# BatteryBalancer_old.net
KiCad netlist of a schematic drawn in EAGLE
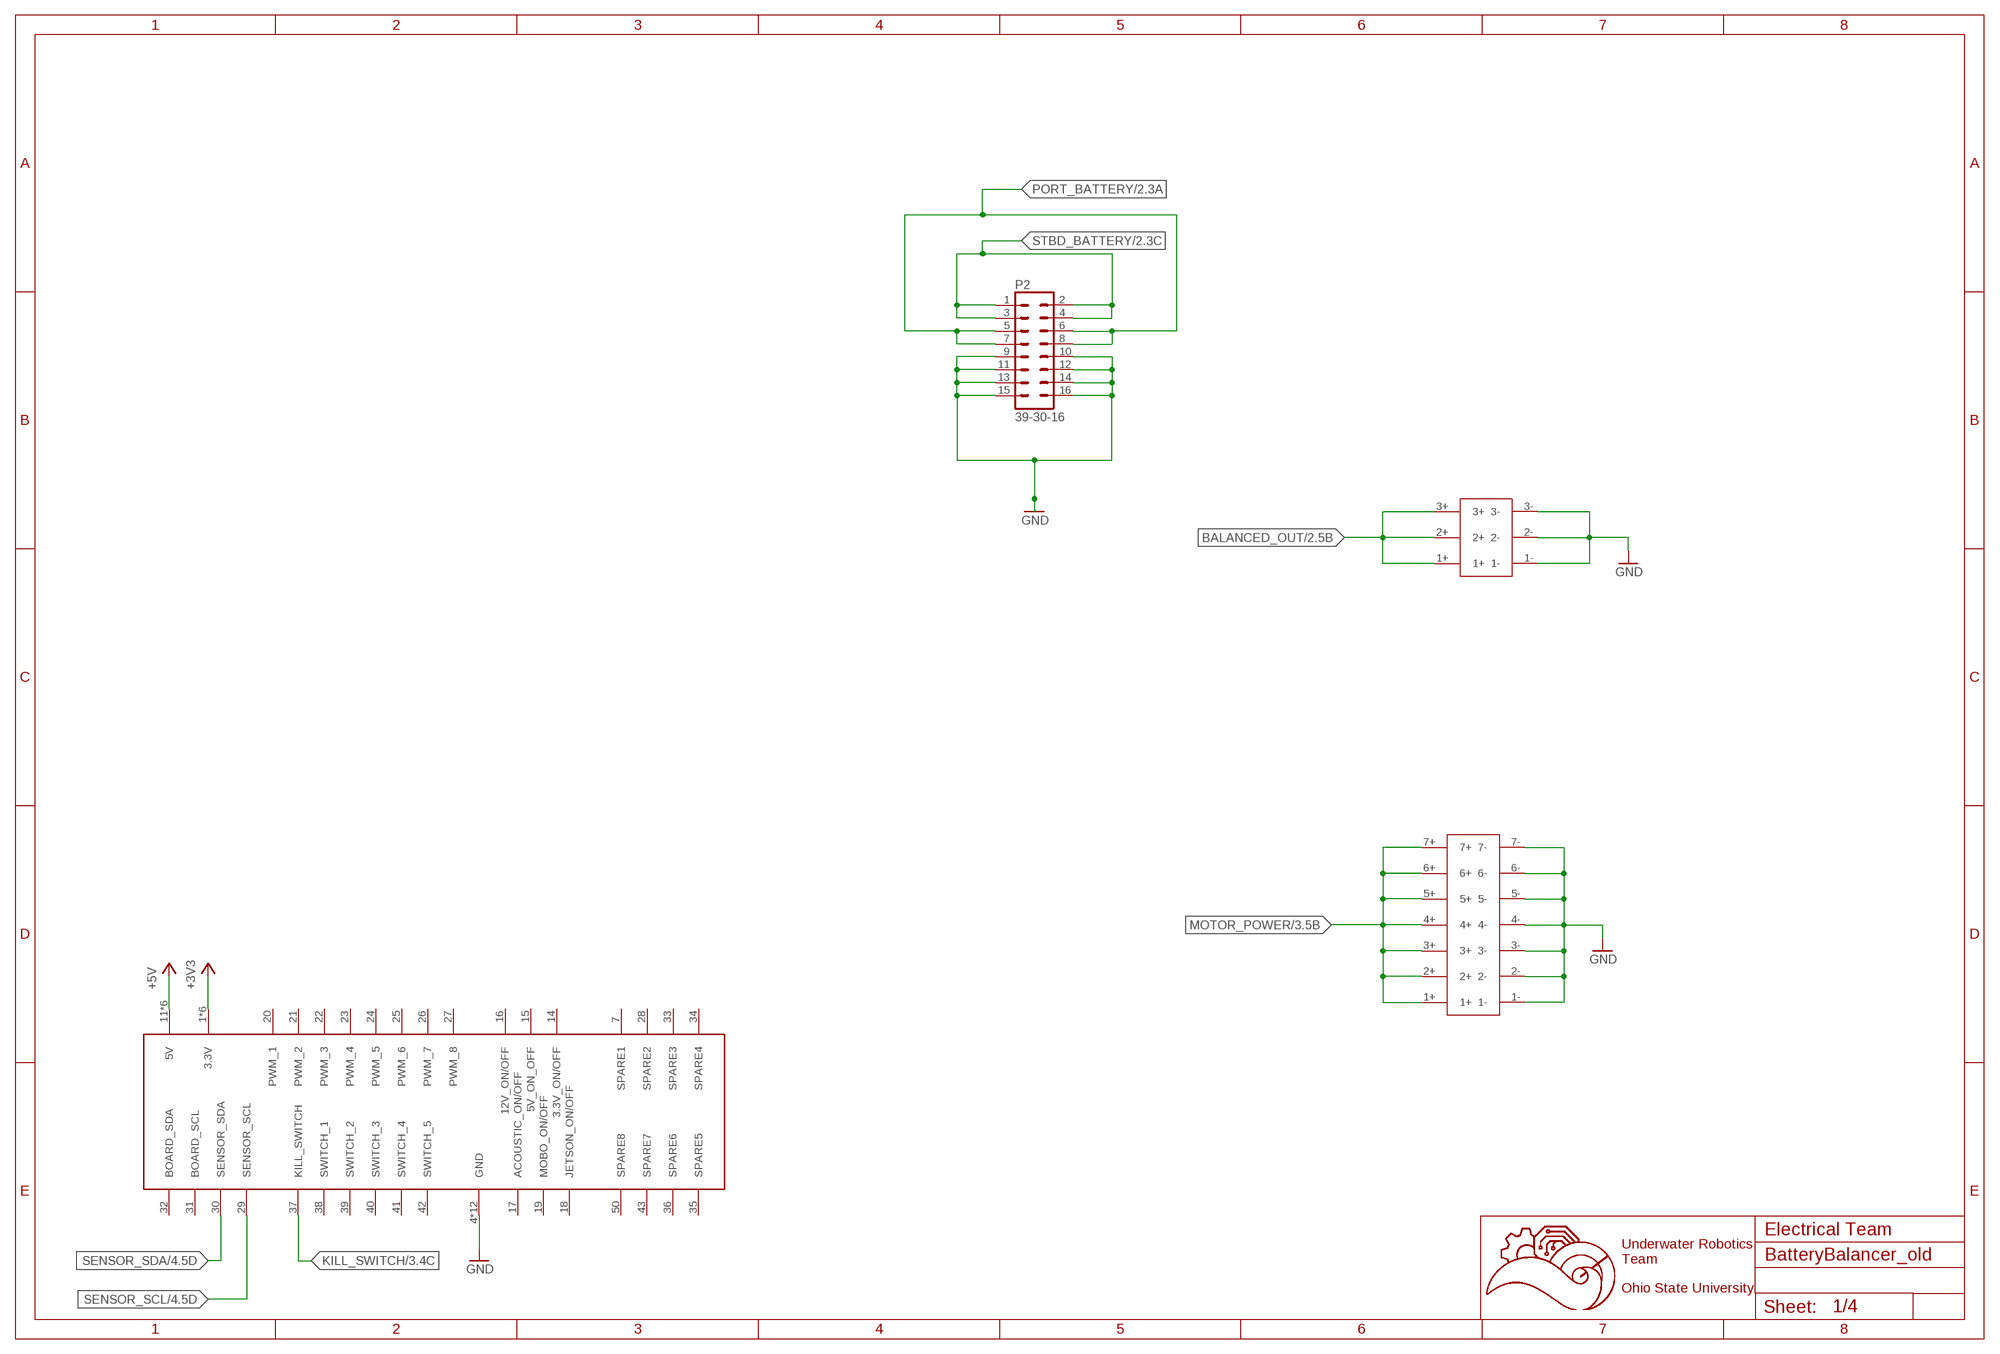
[diagram p0: schematic, sheet 1]
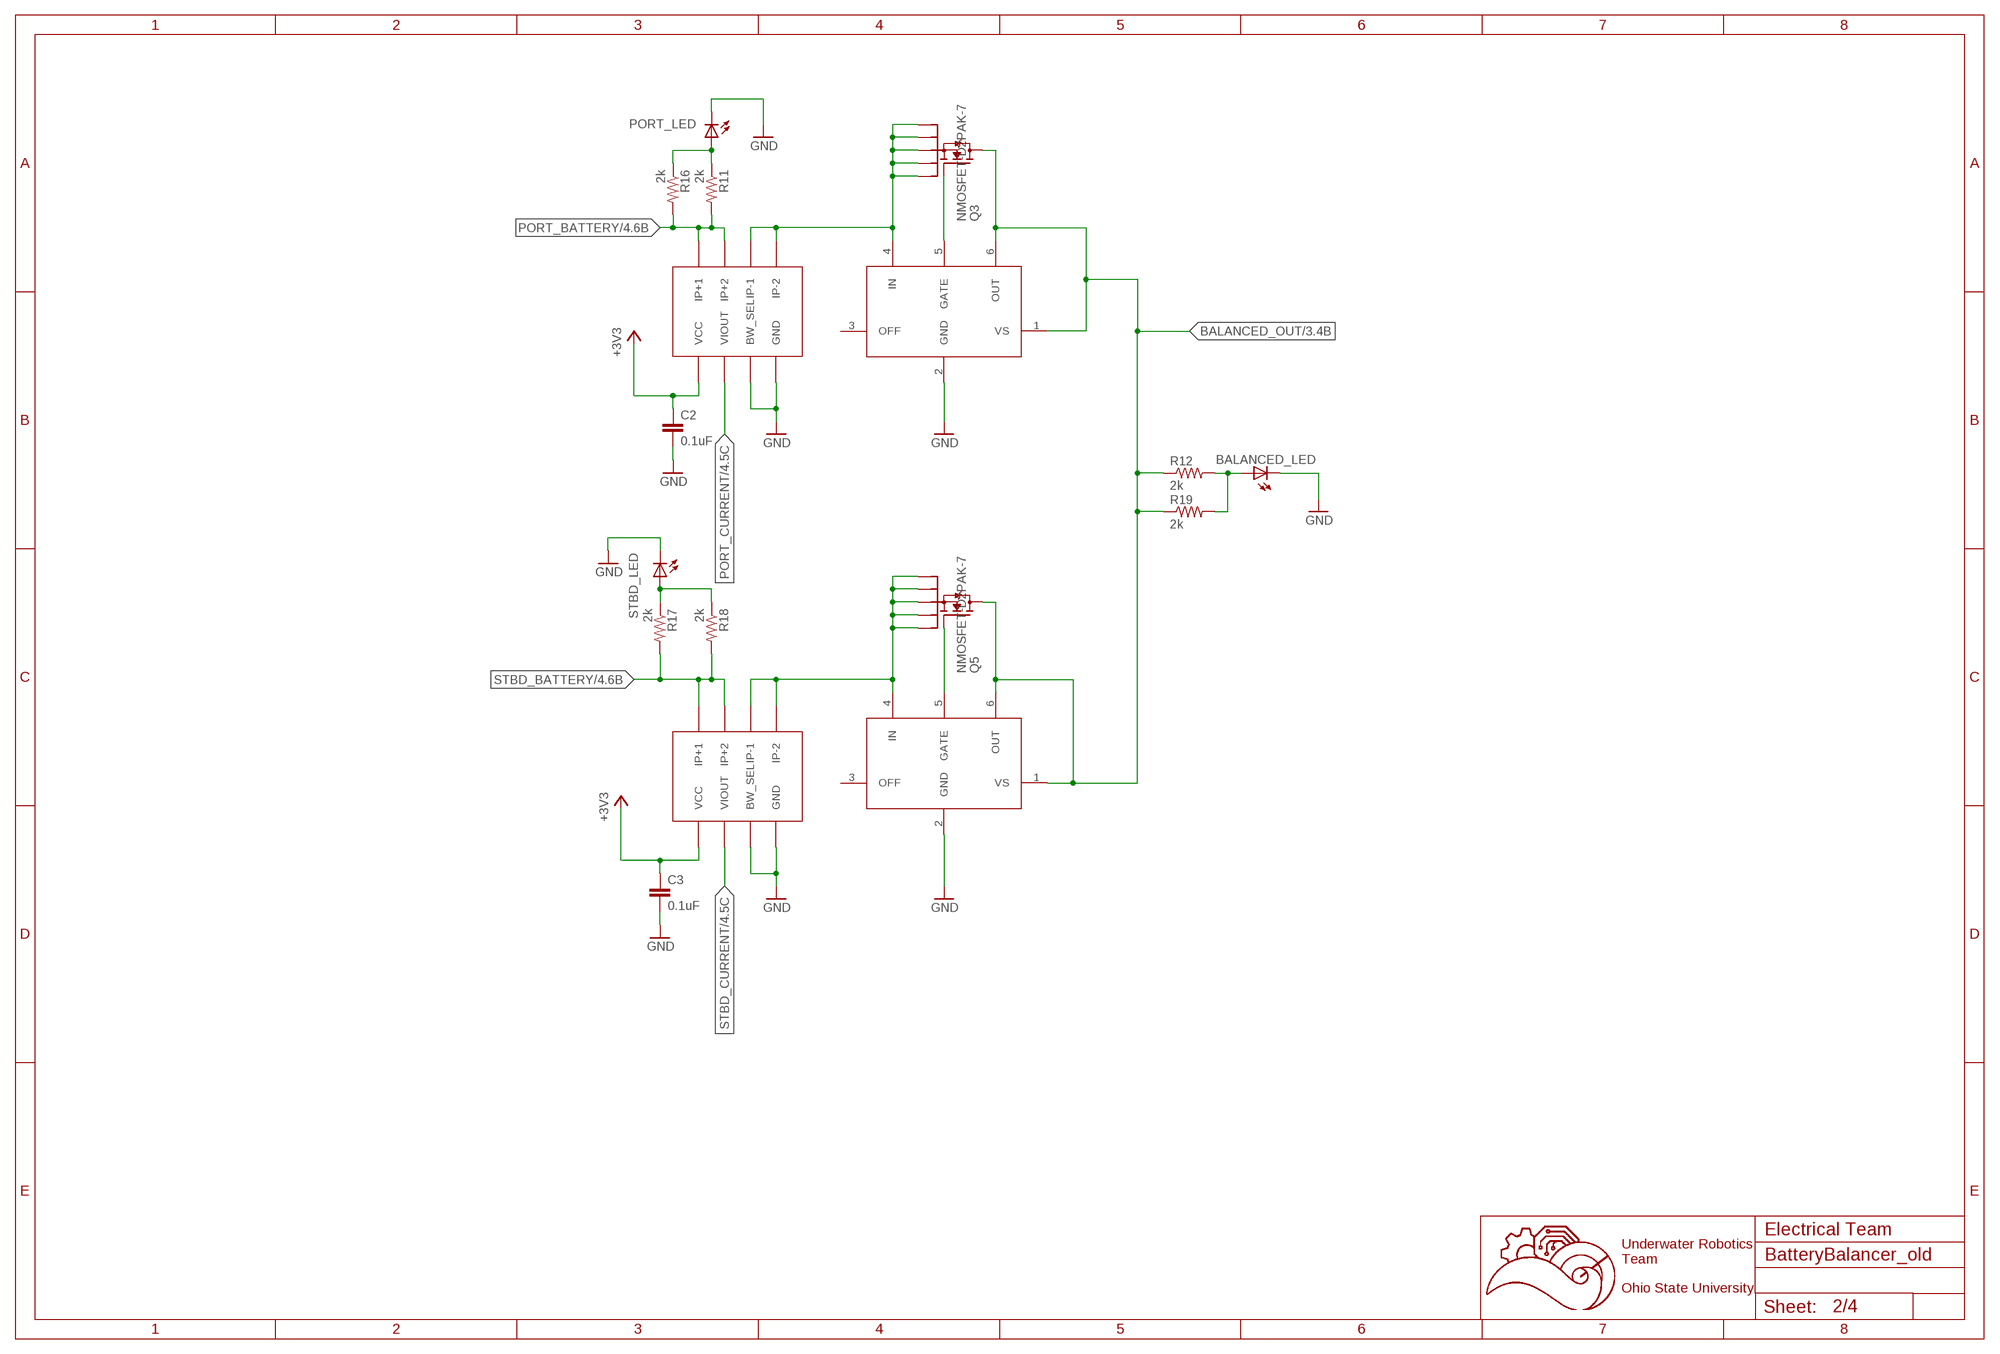
[diagram p1: schematic, sheet 2]
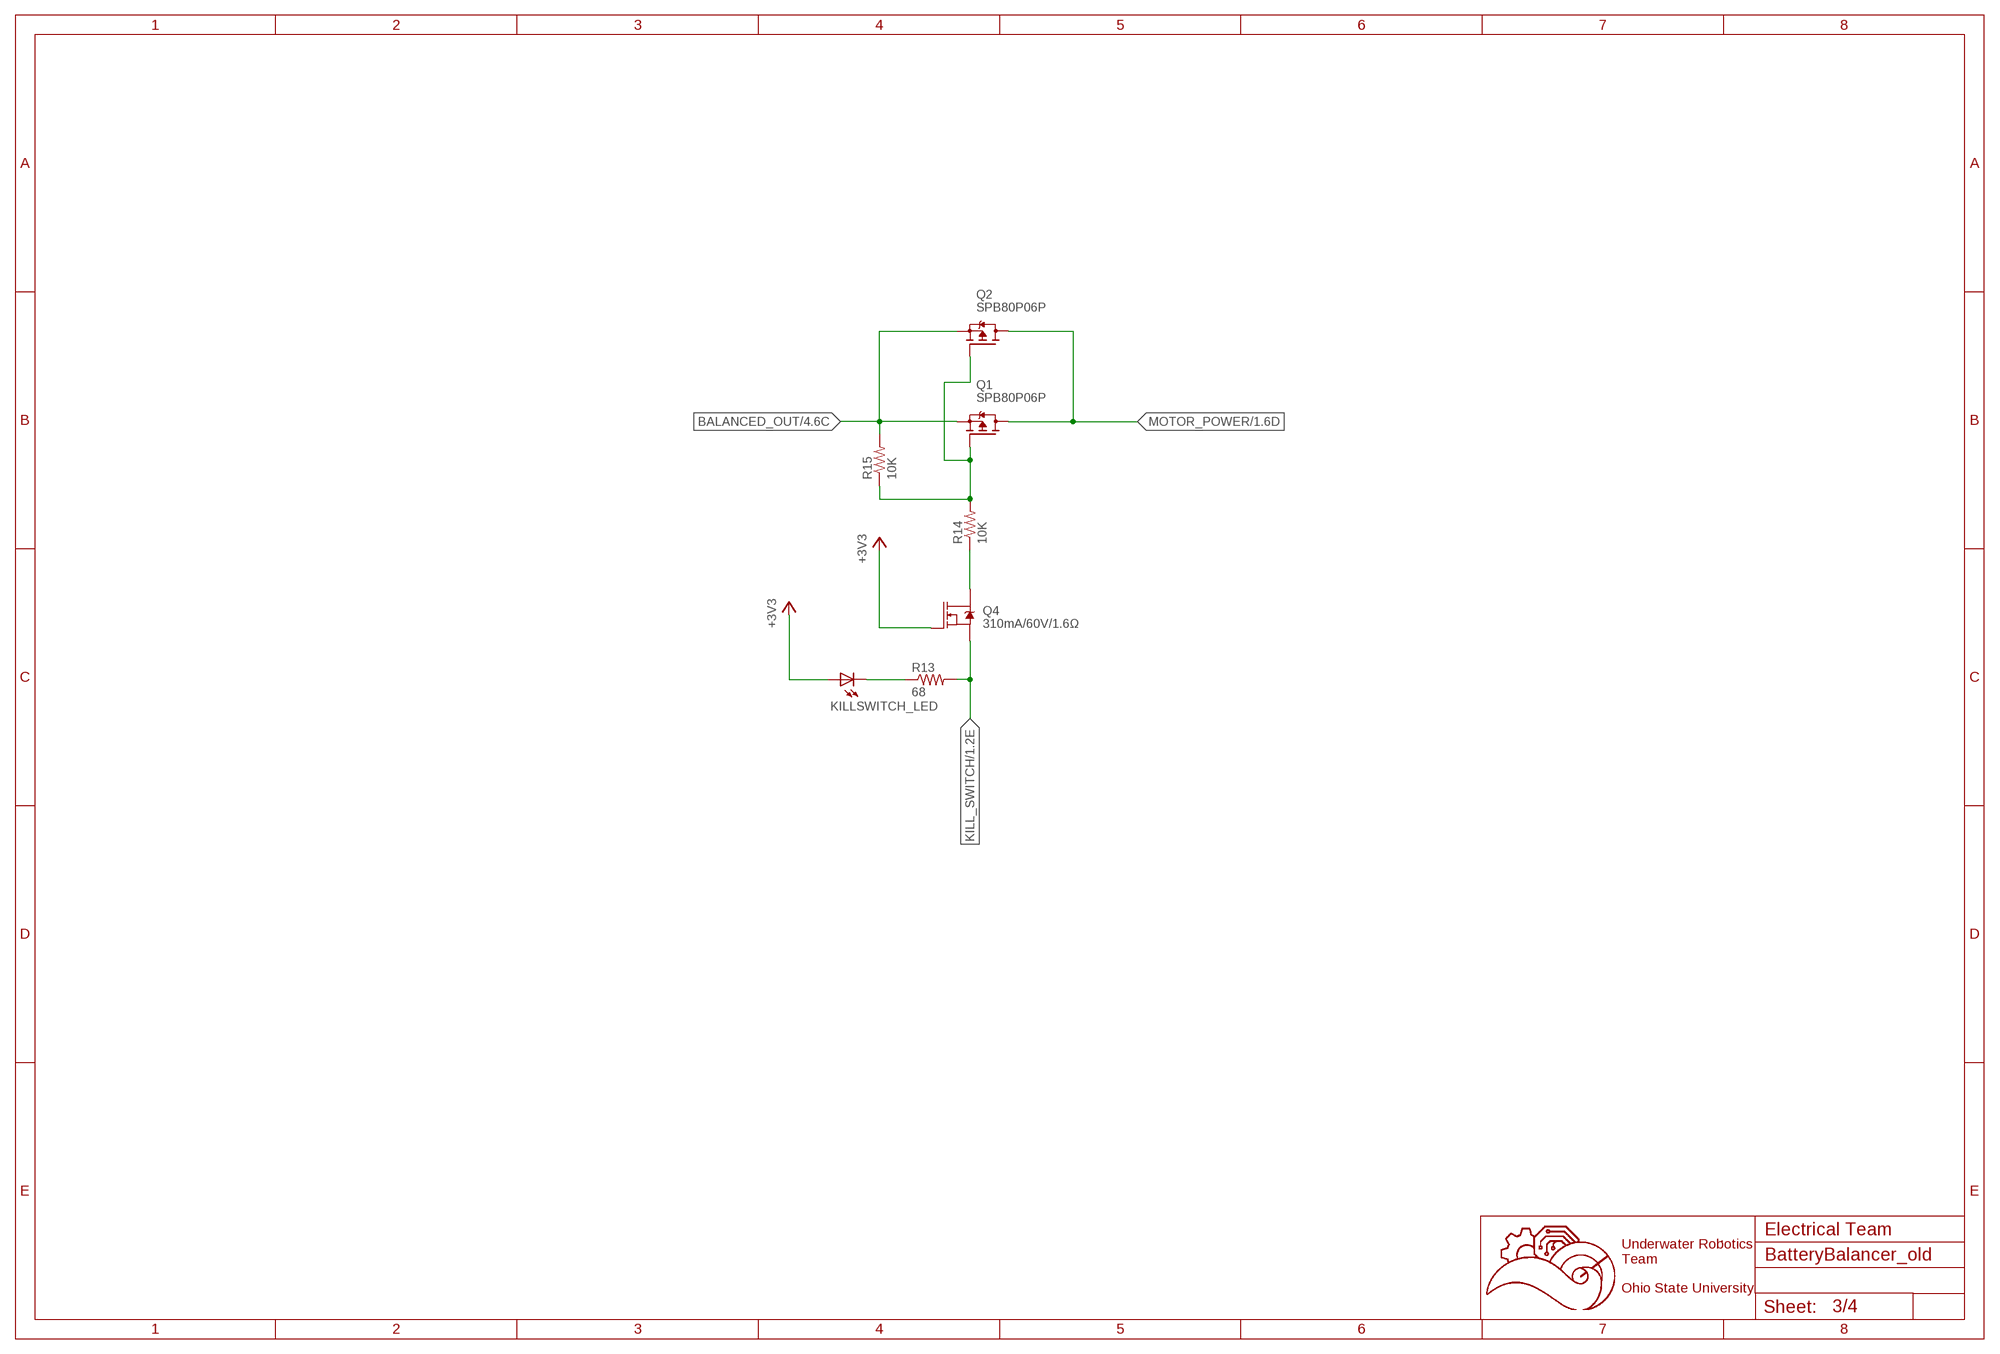
[diagram p2: schematic, sheet 3]
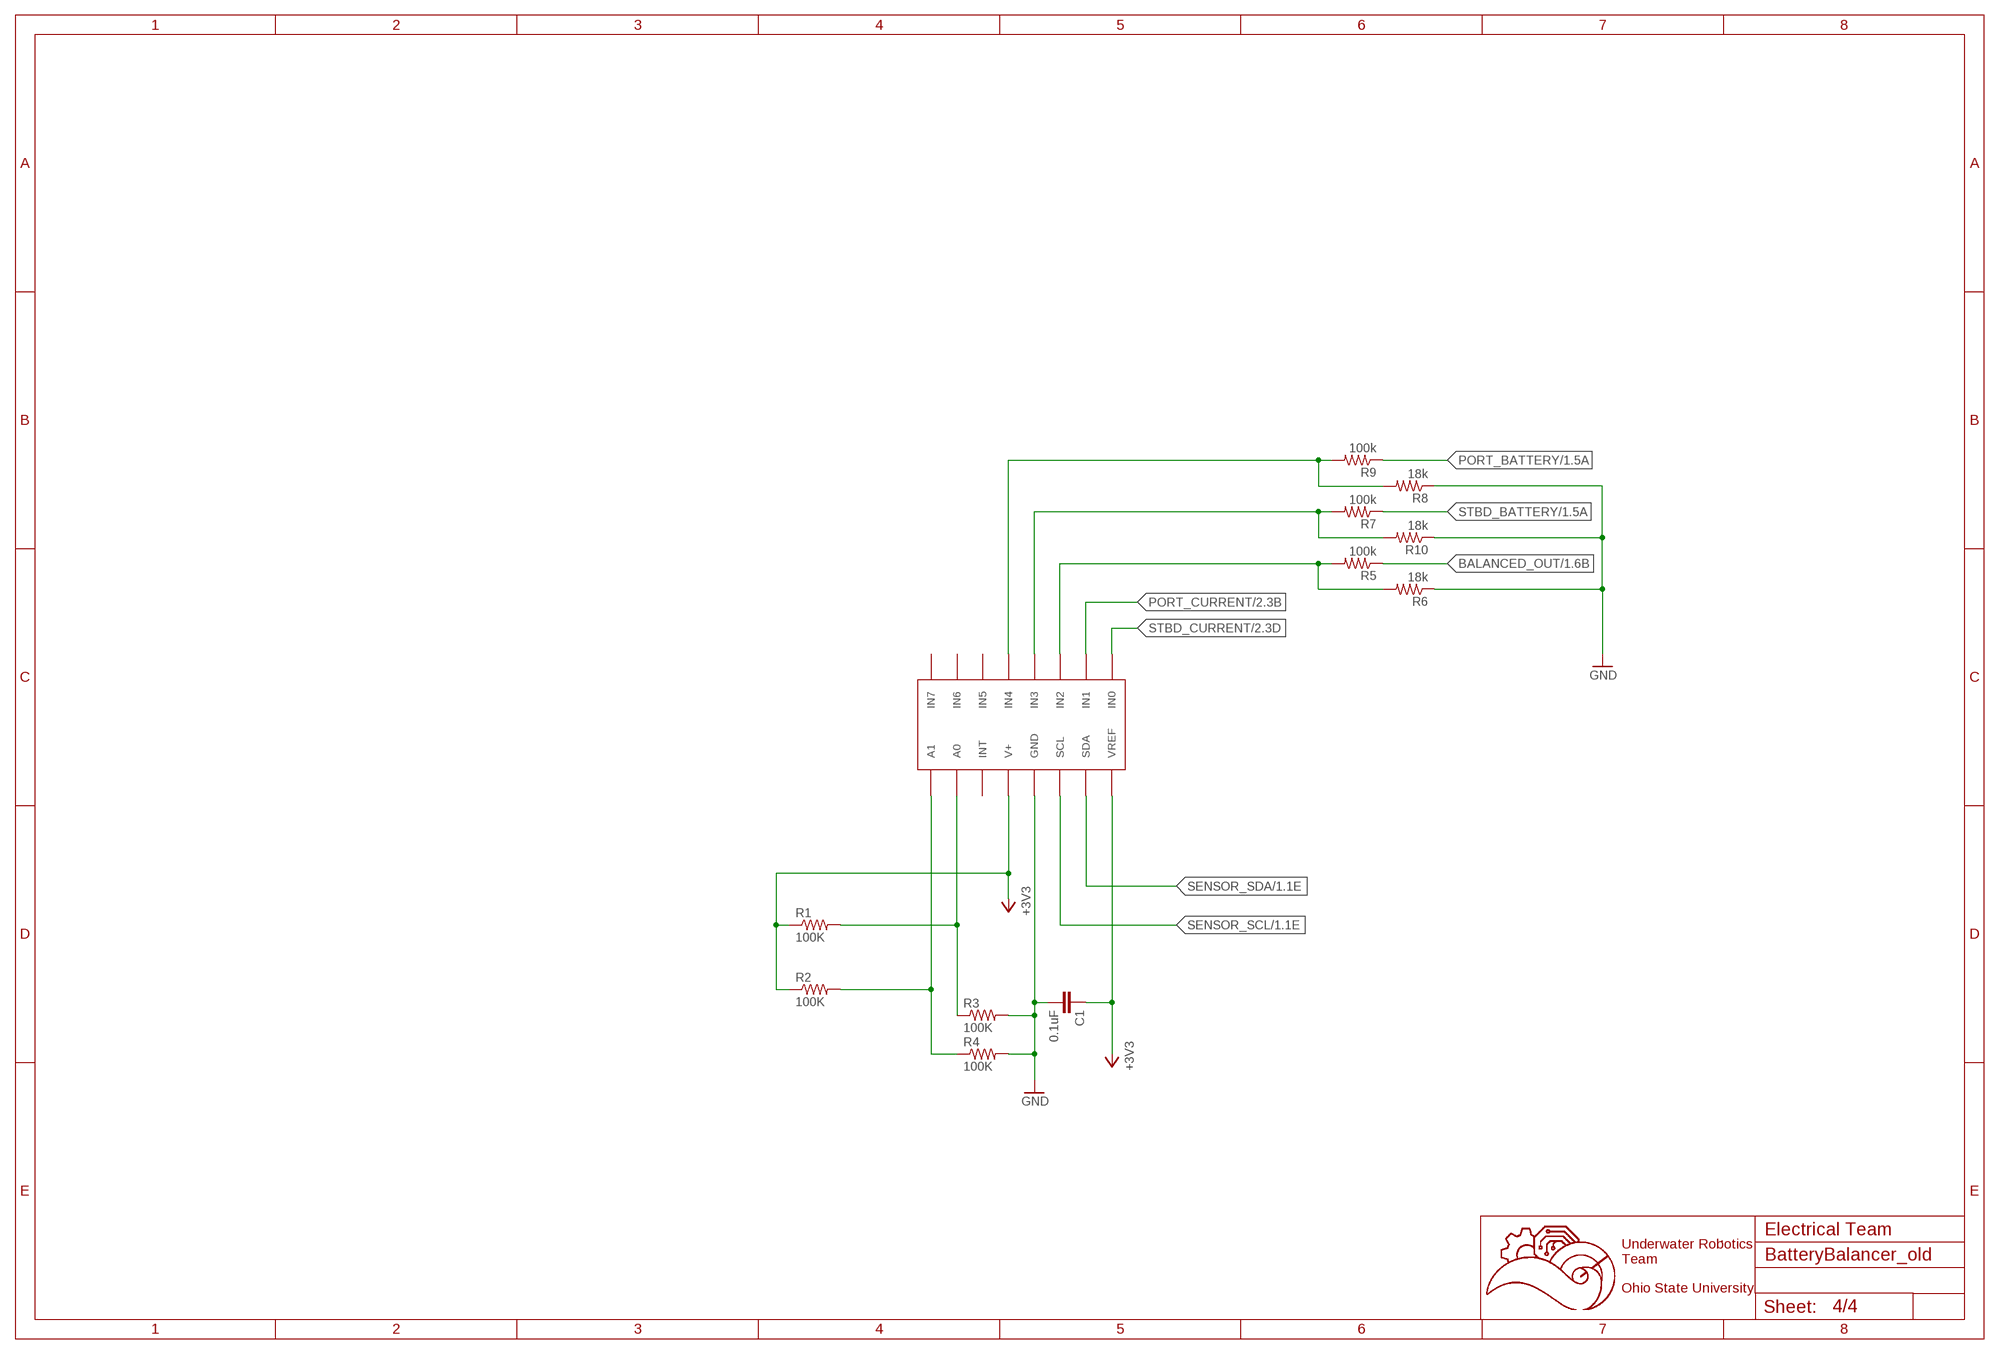
[diagram p3: schematic, sheet 4]

(export (version "E")
  (design (tool "Eeschema 10.0.6"))
  (components
    (comp (ref "C1")
      (value "0.1uF")
      (footprint "eagle-import:C0603")
      (libsource (lib "eagle-import") (part "C-EUC0603"))
    )
    (comp (ref "R1")
      (value "100K")
      (footprint "eagle-import:R0603")
      (libsource (lib "eagle-import") (part "R-US_R0603"))
    )
    (comp (ref "R2")
      (value "100K")
      (footprint "eagle-import:R0603")
      (libsource (lib "eagle-import") (part "R-US_R0603"))
    )
    (comp (ref "R3")
      (value "100K")
      (footprint "eagle-import:R0603")
      (libsource (lib "eagle-import") (part "R-US_R0603"))
    )
    (comp (ref "R4")
      (value "100K")
      (footprint "eagle-import:R0603")
      (libsource (lib "eagle-import") (part "R-US_R0603"))
    )
    (comp (ref "R5")
      (value "100k")
      (footprint "eagle-import:R0603")
      (libsource (lib "eagle-import") (part "R-US_R0603"))
    )
    (comp (ref "R6")
      (value "18k")
      (footprint "eagle-import:R0603")
      (libsource (lib "eagle-import") (part "R-US_R0603"))
    )
    (comp (ref "R7")
      (value "100k")
      (footprint "eagle-import:R0603")
      (libsource (lib "eagle-import") (part "R-US_R0603"))
    )
    (comp (ref "R8")
      (value "18k")
      (footprint "eagle-import:R0603")
      (libsource (lib "eagle-import") (part "R-US_R0603"))
    )
    (comp (ref "R9")
      (value "100k")
      (footprint "eagle-import:R0603")
      (libsource (lib "eagle-import") (part "R-US_R0603"))
    )
    (comp (ref "R10")
      (value "18k")
      (footprint "eagle-import:R0603")
      (libsource (lib "eagle-import") (part "R-US_R0603"))
    )
    (comp (ref "U$12")
      (value "ADC128D818")
      (footprint "eagle-import:TSSOP-16")
      (libsource (lib "eagle-import") (part "ADC128D818"))
    )
    (comp (ref "KILLSWITCH_LED")
      (value "LEDCHIP-LED0603")
      (footprint "eagle-import:CHIP-LED0603")
      (libsource (lib "eagle-import") (part "LEDCHIP-LED0603"))
    )
    (comp (ref "Q1")
      (value "SPB80P06P")
      (footprint "eagle-import:TO263")
      (libsource (lib "eagle-import") (part "SPB80P06P"))
    )
    (comp (ref "Q2")
      (value "SPB80P06P")
      (footprint "eagle-import:TO263")
      (libsource (lib "eagle-import") (part "SPB80P06P"))
    )
    (comp (ref "Q4")
      (value "310mA/60V/1.6Ω")
      (footprint "eagle-import:SOT323")
      (libsource (lib "eagle-import") (part "MOSFET-NCH-2N7002PW"))
    )
    (comp (ref "R13")
      (value "68")
      (footprint "eagle-import:R0603")
      (libsource (lib "eagle-import") (part "R-US_R0603"))
    )
    (comp (ref "R14")
      (value "10K")
      (footprint "eagle-import:R0603")
      (libsource (lib "eagle-import") (part "R-US_R0603"))
    )
    (comp (ref "R15")
      (value "10K")
      (footprint "eagle-import:R0603")
      (libsource (lib "eagle-import") (part "R-US_R0603"))
    )
    (comp (ref "P2")
      (value "39-30-16")
      (footprint "eagle-import:39-30-_16_")
      (libsource (lib "eagle-import") (part "39-30-?16?"))
    )
    (comp (ref "U$1")
      (value "5530843-EDGE")
      (footprint "eagle-import:5530843-6-BOARDFINGERS")
      (libsource (lib "eagle-import") (part "5530843-EDGE"))
    )
    (comp (ref "U$4")
      (value "14PIN-VERT")
      (footprint "eagle-import:14PIN_VERT")
      (libsource (lib "eagle-import") (part "14PIN-VERT"))
    )
    (comp (ref "U$13")
      (value "6PIN-VERT")
      (footprint "eagle-import:6PIN_VERT")
      (libsource (lib "eagle-import") (part "6PIN-VERT"))
    )
    (comp (ref "BALANCED_LED")
      (value "LEDCHIP-LED0603")
      (footprint "eagle-import:CHIP-LED0603")
      (libsource (lib "eagle-import") (part "LEDCHIP-LED0603"))
    )
    (comp (ref "C2")
      (value "0.1uF")
      (footprint "eagle-import:C0603")
      (libsource (lib "eagle-import") (part "C-EUC0603"))
    )
    (comp (ref "C3")
      (value "0.1uF")
      (footprint "eagle-import:C0603")
      (libsource (lib "eagle-import") (part "C-EUC0603"))
    )
    (comp (ref "PORT_LED")
      (value "LEDCHIP-LED0603")
      (footprint "eagle-import:CHIP-LED0603")
      (libsource (lib "eagle-import") (part "LEDCHIP-LED0603"))
    )
    (comp (ref "Q3")
      (value "NMOSFET-D2PAK-7")
      (footprint "eagle-import:D2PAK-7")
      (libsource (lib "eagle-import") (part "NMOSFET-D2PAK-7"))
    )
    (comp (ref "Q5")
      (value "NMOSFET-D2PAK-7")
      (footprint "eagle-import:D2PAK-7")
      (libsource (lib "eagle-import") (part "NMOSFET-D2PAK-7"))
    )
    (comp (ref "R11")
      (value "2k")
      (footprint "eagle-import:R0603")
      (libsource (lib "eagle-import") (part "R-US_R0603"))
    )
    (comp (ref "R12")
      (value "2k")
      (footprint "eagle-import:R0603")
      (libsource (lib "eagle-import") (part "R-US_R0603"))
    )
    (comp (ref "R16")
      (value "2k")
      (footprint "eagle-import:R0603")
      (libsource (lib "eagle-import") (part "R-US_R0603"))
    )
    (comp (ref "R17")
      (value "2k")
      (footprint "eagle-import:R0603")
      (libsource (lib "eagle-import") (part "R-US_R0603"))
    )
    (comp (ref "R18")
      (value "2k")
      (footprint "eagle-import:R0603")
      (libsource (lib "eagle-import") (part "R-US_R0603"))
    )
    (comp (ref "R19")
      (value "2k")
      (footprint "eagle-import:R0603")
      (libsource (lib "eagle-import") (part "R-US_R0603"))
    )
    (comp (ref "STBD_LED")
      (value "LEDCHIP-LED0603")
      (footprint "eagle-import:CHIP-LED0603")
      (libsource (lib "eagle-import") (part "LEDCHIP-LED0603"))
    )
    (comp (ref "U$2")
      (value "LM5050")
      (footprint "eagle-import:LM5050")
      (libsource (lib "eagle-import") (part "LM5050"))
    )
    (comp (ref "U$3")
      (value "LM5050")
      (footprint "eagle-import:LM5050")
      (libsource (lib "eagle-import") (part "LM5050"))
    )
    (comp (ref "U$6")
      (value "ACS722")
      (footprint "eagle-import:SOIC-8")
      (libsource (lib "eagle-import") (part "ACS722"))
    )
    (comp (ref "U$7")
      (value "ACS722")
      (footprint "eagle-import:SOIC-8")
      (libsource (lib "eagle-import") (part "ACS722"))
    )
  )
  (nets
    (net (code "1") (name "+3V3") (class "Default")
      (node (ref "C1") (pin "1") (pinfunction "1_1") (pintype "passive"))
      (node (ref "C2") (pin "1") (pinfunction "1_1") (pintype "passive"))
      (node (ref "C3") (pin "1") (pinfunction "1_1") (pintype "passive"))
      (node (ref "KILLSWITCH_LED") (pin "A") (pinfunction "A_A") (pintype "passive"))
      (node (ref "Q4") (pin "1") (pinfunction "G_1") (pintype "bidirectional"))
      (node (ref "R1") (pin "1") (pinfunction "1_1") (pintype "passive"))
      (node (ref "R2") (pin "1") (pinfunction "1_1") (pintype "passive"))
      (node (ref "U$1") (pin "1") (pinfunction "3.3V_1") (pintype "bidirectional"))
      (node (ref "U$1") (pin "2") (pinfunction "3.3V_2") (pintype "bidirectional"))
      (node (ref "U$1") (pin "3") (pinfunction "3.3V_3") (pintype "bidirectional"))
      (node (ref "U$1") (pin "54") (pinfunction "3.3V_54") (pintype "bidirectional"))
      (node (ref "U$1") (pin "55") (pinfunction "3.3V_55") (pintype "bidirectional"))
      (node (ref "U$1") (pin "56") (pinfunction "3.3V_56") (pintype "bidirectional"))
      (node (ref "U$12") (pin "V+") (pinfunction "V+_V+") (pintype "bidirectional"))
      (node (ref "U$12") (pin "VREF") (pinfunction "VREF_VREF") (pintype "bidirectional"))
      (node (ref "U$6") (pin "VCC") (pinfunction "VCC_VCC") (pintype "bidirectional"))
      (node (ref "U$7") (pin "VCC") (pinfunction "VCC_VCC") (pintype "bidirectional"))
    )
    (net (code "2") (name "+5V") (class "Default")
      (node (ref "U$1") (pin "11") (pinfunction "5V_11") (pintype "bidirectional"))
      (node (ref "U$1") (pin "12") (pinfunction "5V_12") (pintype "bidirectional"))
      (node (ref "U$1") (pin "13") (pinfunction "5V_13") (pintype "bidirectional"))
      (node (ref "U$1") (pin "44") (pinfunction "5V_44") (pintype "bidirectional"))
      (node (ref "U$1") (pin "45") (pinfunction "5V_45") (pintype "bidirectional"))
      (node (ref "U$1") (pin "46") (pinfunction "5V_46") (pintype "bidirectional"))
    )
    (net (code "3") (name "BALANCED_OUT") (class "Default")
      (node (ref "Q1") (pin "2") (pinfunction "S_2") (pintype "passive"))
      (node (ref "Q2") (pin "2") (pinfunction "S_2") (pintype "passive"))
      (node (ref "Q3") (pin "D") (pinfunction "D_D") (pintype "passive"))
      (node (ref "Q5") (pin "D") (pinfunction "D_D") (pintype "passive"))
      (node (ref "R12") (pin "1") (pinfunction "1_1") (pintype "passive"))
      (node (ref "R15") (pin "2") (pinfunction "2_2") (pintype "passive"))
      (node (ref "R19") (pin "1") (pinfunction "1_1") (pintype "passive"))
      (node (ref "R5") (pin "1") (pinfunction "1_1") (pintype "passive"))
      (node (ref "U$13") (pin "1+") (pinfunction "1+_1+") (pintype "bidirectional"))
      (node (ref "U$13") (pin "2+") (pinfunction "2+_2+") (pintype "bidirectional"))
      (node (ref "U$13") (pin "3+") (pinfunction "3+_3+") (pintype "bidirectional"))
      (node (ref "U$2") (pin "1") (pinfunction "VS_1") (pintype "bidirectional"))
      (node (ref "U$2") (pin "6") (pinfunction "OUT_6") (pintype "bidirectional"))
      (node (ref "U$3") (pin "1") (pinfunction "VS_1") (pintype "bidirectional"))
      (node (ref "U$3") (pin "6") (pinfunction "OUT_6") (pintype "bidirectional"))
    )
    (net (code "4") (name "GND") (class "Default")
      (node (ref "BALANCED_LED") (pin "C") (pinfunction "C_C") (pintype "passive"))
      (node (ref "C1") (pin "2") (pinfunction "2_2") (pintype "passive"))
      (node (ref "C2") (pin "2") (pinfunction "2_2") (pintype "passive"))
      (node (ref "C3") (pin "2") (pinfunction "2_2") (pintype "passive"))
      (node (ref "P2") (pin "10") (pinfunction "10_10") (pintype "passive"))
      (node (ref "P2") (pin "11") (pinfunction "11_11") (pintype "passive"))
      (node (ref "P2") (pin "12") (pinfunction "12_12") (pintype "passive"))
      (node (ref "P2") (pin "13") (pinfunction "13_13") (pintype "passive"))
      (node (ref "P2") (pin "14") (pinfunction "14_14") (pintype "passive"))
      (node (ref "P2") (pin "15") (pinfunction "15_15") (pintype "passive"))
      (node (ref "P2") (pin "16") (pinfunction "16_16") (pintype "passive"))
      (node (ref "P2") (pin "9") (pinfunction "9_9") (pintype "passive"))
      (node (ref "PORT_LED") (pin "C") (pinfunction "C_C") (pintype "passive"))
      (node (ref "R10") (pin "1") (pinfunction "1_1") (pintype "passive"))
      (node (ref "R3") (pin "2") (pinfunction "2_2") (pintype "passive"))
      (node (ref "R4") (pin "2") (pinfunction "2_2") (pintype "passive"))
      (node (ref "R6") (pin "1") (pinfunction "1_1") (pintype "passive"))
      (node (ref "R8") (pin "1") (pinfunction "1_1") (pintype "passive"))
      (node (ref "STBD_LED") (pin "C") (pinfunction "C_C") (pintype "passive"))
      (node (ref "U$1") (pin "10") (pinfunction "GND_10") (pintype "bidirectional"))
      (node (ref "U$1") (pin "4") (pinfunction "GND_4") (pintype "bidirectional"))
      (node (ref "U$1") (pin "47") (pinfunction "GND_47") (pintype "bidirectional"))
      (node (ref "U$1") (pin "48") (pinfunction "GND_48") (pintype "bidirectional"))
      (node (ref "U$1") (pin "49") (pinfunction "GND_49") (pintype "bidirectional"))
      (node (ref "U$1") (pin "5") (pinfunction "GND_5") (pintype "bidirectional"))
      (node (ref "U$1") (pin "51") (pinfunction "GND_51") (pintype "bidirectional"))
      (node (ref "U$1") (pin "52") (pinfunction "GND_52") (pintype "bidirectional"))
      (node (ref "U$1") (pin "53") (pinfunction "GND_53") (pintype "bidirectional"))
      (node (ref "U$1") (pin "6") (pinfunction "GND_6") (pintype "bidirectional"))
      (node (ref "U$1") (pin "8") (pinfunction "GND_8") (pintype "bidirectional"))
      (node (ref "U$1") (pin "9") (pinfunction "GND_9") (pintype "bidirectional"))
      (node (ref "U$12") (pin "GND") (pinfunction "GND_GND") (pintype "bidirectional"))
      (node (ref "U$13") (pin "1-") (pinfunction "1-_1-") (pintype "bidirectional"))
      (node (ref "U$13") (pin "2-") (pinfunction "2-_2-") (pintype "bidirectional"))
      (node (ref "U$13") (pin "3-") (pinfunction "3-_3-") (pintype "bidirectional"))
      (node (ref "U$2") (pin "2") (pinfunction "GND_2") (pintype "bidirectional"))
      (node (ref "U$3") (pin "2") (pinfunction "GND_2") (pintype "bidirectional"))
      (node (ref "U$4") (pin "1-") (pinfunction "1-_1-") (pintype "bidirectional"))
      (node (ref "U$4") (pin "2-") (pinfunction "2-_2-") (pintype "bidirectional"))
      (node (ref "U$4") (pin "3-") (pinfunction "3-_3-") (pintype "bidirectional"))
      (node (ref "U$4") (pin "4-") (pinfunction "4-_4-") (pintype "bidirectional"))
      (node (ref "U$4") (pin "5-") (pinfunction "5-_5-") (pintype "bidirectional"))
      (node (ref "U$4") (pin "6-") (pinfunction "6-_6-") (pintype "bidirectional"))
      (node (ref "U$4") (pin "7-") (pinfunction "7-_7-") (pintype "bidirectional"))
      (node (ref "U$6") (pin "BW_SEL") (pinfunction "BW_SEL_BW_SEL") (pintype "bidirectional"))
      (node (ref "U$6") (pin "GND") (pinfunction "GND_GND") (pintype "bidirectional"))
      (node (ref "U$7") (pin "BW_SEL") (pinfunction "BW_SEL_BW_SEL") (pintype "bidirectional"))
      (node (ref "U$7") (pin "GND") (pinfunction "GND_GND") (pintype "bidirectional"))
    )
    (net (code "5") (name "KILL_SWITCH") (class "Default")
      (node (ref "Q4") (pin "2") (pinfunction "S_2") (pintype "bidirectional"))
      (node (ref "R13") (pin "2") (pinfunction "2_2") (pintype "passive"))
      (node (ref "U$1") (pin "37") (pinfunction "KILL_SWITCH_37") (pintype "output"))
    )
    (net (code "6") (name "MOTOR_POWER") (class "Default")
      (node (ref "Q1") (pin "3") (pinfunction "D_3") (pintype "passive"))
      (node (ref "Q2") (pin "3") (pinfunction "D_3") (pintype "passive"))
      (node (ref "U$4") (pin "1+") (pinfunction "1+_1+") (pintype "bidirectional"))
      (node (ref "U$4") (pin "2+") (pinfunction "2+_2+") (pintype "bidirectional"))
      (node (ref "U$4") (pin "3+") (pinfunction "3+_3+") (pintype "bidirectional"))
      (node (ref "U$4") (pin "4+") (pinfunction "4+_4+") (pintype "bidirectional"))
      (node (ref "U$4") (pin "5+") (pinfunction "5+_5+") (pintype "bidirectional"))
      (node (ref "U$4") (pin "6+") (pinfunction "6+_6+") (pintype "bidirectional"))
      (node (ref "U$4") (pin "7+") (pinfunction "7+_7+") (pintype "bidirectional"))
    )
    (net (code "7") (name "Net-(BALANCED_LED-PadA)") (class "Default")
      (node (ref "BALANCED_LED") (pin "A") (pinfunction "A_A") (pintype "passive"))
      (node (ref "R12") (pin "2") (pinfunction "2_2") (pintype "passive"))
      (node (ref "R19") (pin "2") (pinfunction "2_2") (pintype "passive"))
    )
    (net (code "8") (name "Net-(KILLSWITCH_LED-PadC)") (class "Default")
      (node (ref "KILLSWITCH_LED") (pin "C") (pinfunction "C_C") (pintype "passive"))
      (node (ref "R13") (pin "1") (pinfunction "1_1") (pintype "passive"))
    )
    (net (code "9") (name "Net-(PORT_LED-PadA)") (class "Default")
      (node (ref "PORT_LED") (pin "A") (pinfunction "A_A") (pintype "passive"))
      (node (ref "R11") (pin "1") (pinfunction "1_1") (pintype "passive"))
      (node (ref "R16") (pin "1") (pinfunction "1_1") (pintype "passive"))
    )
    (net (code "10") (name "Net-(Q1-G)") (class "Default")
      (node (ref "Q1") (pin "1") (pinfunction "G_1") (pintype "passive"))
      (node (ref "Q2") (pin "1") (pinfunction "G_1") (pintype "passive"))
      (node (ref "R14") (pin "2") (pinfunction "2_2") (pintype "passive"))
      (node (ref "R15") (pin "1") (pinfunction "1_1") (pintype "passive"))
    )
    (net (code "11") (name "Net-(Q4-D)") (class "Default")
      (node (ref "Q4") (pin "3") (pinfunction "D_3") (pintype "bidirectional"))
      (node (ref "R14") (pin "1") (pinfunction "1_1") (pintype "passive"))
    )
    (net (code "12") (name "Net-(R1-Pad2)") (class "Default")
      (node (ref "R1") (pin "2") (pinfunction "2_2") (pintype "passive"))
      (node (ref "R3") (pin "1") (pinfunction "1_1") (pintype "passive"))
      (node (ref "U$12") (pin "A0") (pinfunction "A0_A0") (pintype "bidirectional"))
    )
    (net (code "13") (name "Net-(R2-Pad2)") (class "Default")
      (node (ref "R2") (pin "2") (pinfunction "2_2") (pintype "passive"))
      (node (ref "R4") (pin "1") (pinfunction "1_1") (pintype "passive"))
      (node (ref "U$12") (pin "A1") (pinfunction "A1_A1") (pintype "bidirectional"))
    )
    (net (code "14") (name "Net-(R5-Pad2)") (class "Default")
      (node (ref "R5") (pin "2") (pinfunction "2_2") (pintype "passive"))
      (node (ref "R6") (pin "2") (pinfunction "2_2") (pintype "passive"))
      (node (ref "U$12") (pin "IN2") (pinfunction "IN2_IN2") (pintype "bidirectional"))
    )
    (net (code "15") (name "Net-(R8-Pad2)") (class "Default")
      (node (ref "R8") (pin "2") (pinfunction "2_2") (pintype "passive"))
      (node (ref "R9") (pin "2") (pinfunction "2_2") (pintype "passive"))
      (node (ref "U$12") (pin "IN4") (pinfunction "IN4_IN4") (pintype "bidirectional"))
    )
    (net (code "16") (name "Net-(R10-Pad2)") (class "Default")
      (node (ref "R10") (pin "2") (pinfunction "2_2") (pintype "passive"))
      (node (ref "R7") (pin "2") (pinfunction "2_2") (pintype "passive"))
      (node (ref "U$12") (pin "IN3") (pinfunction "IN3_IN3") (pintype "bidirectional"))
    )
    (net (code "17") (name "Net-(R17-Pad1)") (class "Default")
      (node (ref "R17") (pin "1") (pinfunction "1_1") (pintype "passive"))
      (node (ref "R18") (pin "1") (pinfunction "1_1") (pintype "passive"))
      (node (ref "STBD_LED") (pin "A") (pinfunction "A_A") (pintype "passive"))
    )
    (net (code "18") (name "Net-(U$2-GATE)") (class "Default")
      (node (ref "Q3") (pin "G") (pinfunction "G_G") (pintype "passive"))
      (node (ref "U$2") (pin "5") (pinfunction "GATE_5") (pintype "bidirectional"))
    )
    (net (code "19") (name "Net-(U$2-IN)") (class "Default")
      (node (ref "Q3") (pin "S1") (pinfunction "S1_S1") (pintype "passive"))
      (node (ref "Q3") (pin "S2") (pinfunction "S2_S2") (pintype "passive"))
      (node (ref "Q3") (pin "S3") (pinfunction "S3_S3") (pintype "passive"))
      (node (ref "Q3") (pin "S4") (pinfunction "S4_S4") (pintype "passive"))
      (node (ref "Q3") (pin "S5") (pinfunction "S5_S5") (pintype "passive"))
      (node (ref "U$2") (pin "4") (pinfunction "IN_4") (pintype "bidirectional"))
      (node (ref "U$6") (pin "IP-1") (pinfunction "IP-1_IP-1") (pintype "bidirectional"))
      (node (ref "U$6") (pin "IP-2") (pinfunction "IP-2_IP-2") (pintype "bidirectional"))
    )
    (net (code "20") (name "Net-(U$3-GATE)") (class "Default")
      (node (ref "Q5") (pin "G") (pinfunction "G_G") (pintype "passive"))
      (node (ref "U$3") (pin "5") (pinfunction "GATE_5") (pintype "bidirectional"))
    )
    (net (code "21") (name "Net-(U$3-IN)") (class "Default")
      (node (ref "Q5") (pin "S1") (pinfunction "S1_S1") (pintype "passive"))
      (node (ref "Q5") (pin "S2") (pinfunction "S2_S2") (pintype "passive"))
      (node (ref "Q5") (pin "S3") (pinfunction "S3_S3") (pintype "passive"))
      (node (ref "Q5") (pin "S4") (pinfunction "S4_S4") (pintype "passive"))
      (node (ref "Q5") (pin "S5") (pinfunction "S5_S5") (pintype "passive"))
      (node (ref "U$3") (pin "4") (pinfunction "IN_4") (pintype "bidirectional"))
      (node (ref "U$7") (pin "IP-1") (pinfunction "IP-1_IP-1") (pintype "bidirectional"))
      (node (ref "U$7") (pin "IP-2") (pinfunction "IP-2_IP-2") (pintype "bidirectional"))
    )
    (net (code "22") (name "PORT_BATTERY") (class "Default")
      (node (ref "P2") (pin "5") (pinfunction "5_5") (pintype "passive"))
      (node (ref "P2") (pin "6") (pinfunction "6_6") (pintype "passive"))
      (node (ref "P2") (pin "7") (pinfunction "7_7") (pintype "passive"))
      (node (ref "P2") (pin "8") (pinfunction "8_8") (pintype "passive"))
      (node (ref "R11") (pin "2") (pinfunction "2_2") (pintype "passive"))
      (node (ref "R16") (pin "2") (pinfunction "2_2") (pintype "passive"))
      (node (ref "R9") (pin "1") (pinfunction "1_1") (pintype "passive"))
      (node (ref "U$6") (pin "IP+1") (pinfunction "IP+1_IP+1") (pintype "bidirectional"))
      (node (ref "U$6") (pin "IP+2") (pinfunction "IP+2_IP+2") (pintype "bidirectional"))
    )
    (net (code "23") (name "PORT_CURRENT") (class "Default")
      (node (ref "U$12") (pin "IN1") (pinfunction "IN1_IN1") (pintype "bidirectional"))
      (node (ref "U$6") (pin "VIOUT") (pinfunction "VIOUT_VIOUT") (pintype "bidirectional"))
    )
    (net (code "24") (name "SENSOR_SCL") (class "Default")
      (node (ref "U$1") (pin "29") (pinfunction "SENSOR_SCL_29") (pintype "bidirectional"))
      (node (ref "U$12") (pin "SCL") (pinfunction "SCL_SCL") (pintype "bidirectional"))
    )
    (net (code "25") (name "SENSOR_SDA") (class "Default")
      (node (ref "U$1") (pin "30") (pinfunction "SENSOR_SDA_30") (pintype "bidirectional"))
      (node (ref "U$12") (pin "SDA") (pinfunction "SDA_SDA") (pintype "bidirectional"))
    )
    (net (code "26") (name "STBD_BATTERY") (class "Default")
      (node (ref "P2") (pin "1") (pinfunction "1_1") (pintype "passive"))
      (node (ref "P2") (pin "2") (pinfunction "2_2") (pintype "passive"))
      (node (ref "P2") (pin "3") (pinfunction "3_3") (pintype "passive"))
      (node (ref "P2") (pin "4") (pinfunction "4_4") (pintype "passive"))
      (node (ref "R17") (pin "2") (pinfunction "2_2") (pintype "passive"))
      (node (ref "R18") (pin "2") (pinfunction "2_2") (pintype "passive"))
      (node (ref "R7") (pin "1") (pinfunction "1_1") (pintype "passive"))
      (node (ref "U$7") (pin "IP+1") (pinfunction "IP+1_IP+1") (pintype "bidirectional"))
      (node (ref "U$7") (pin "IP+2") (pinfunction "IP+2_IP+2") (pintype "bidirectional"))
    )
    (net (code "27") (name "STBD_CURRENT") (class "Default")
      (node (ref "U$12") (pin "IN0") (pinfunction "IN0_IN0") (pintype "bidirectional"))
      (node (ref "U$7") (pin "VIOUT") (pinfunction "VIOUT_VIOUT") (pintype "bidirectional"))
    )
    (net (code "28") (name "unconnected-(U$1-3.3V_ON{slash}OFF-Pad14)") (class "Default")
      (node (ref "U$1") (pin "14") (pinfunction "3.3V_ON/OFF_14") (pintype "bidirectional"))
    )
    (net (code "29") (name "unconnected-(U$1-5V_ON_OFF-Pad15)") (class "Default")
      (node (ref "U$1") (pin "15") (pinfunction "5V_ON_OFF_15") (pintype "bidirectional"))
    )
    (net (code "30") (name "unconnected-(U$1-12V_ON{slash}OFF-Pad16)") (class "Default")
      (node (ref "U$1") (pin "16") (pinfunction "12V_ON/OFF_16") (pintype "bidirectional"))
    )
    (net (code "31") (name "unconnected-(U$1-ACOUSTIC_ON{slash}OFF-Pad17)") (class "Default")
      (node (ref "U$1") (pin "17") (pinfunction "ACOUSTIC_ON/OFF_17") (pintype "bidirectional"))
    )
    (net (code "32") (name "unconnected-(U$1-BOARD_SCL-Pad31)") (class "Default")
      (node (ref "U$1") (pin "31") (pinfunction "BOARD_SCL_31") (pintype "bidirectional"))
    )
    (net (code "33") (name "unconnected-(U$1-BOARD_SDA-Pad32)") (class "Default")
      (node (ref "U$1") (pin "32") (pinfunction "BOARD_SDA_32") (pintype "bidirectional"))
    )
    (net (code "34") (name "unconnected-(U$1-JETSON_ON{slash}OFF-Pad18)") (class "Default")
      (node (ref "U$1") (pin "18") (pinfunction "JETSON_ON/OFF_18") (pintype "bidirectional"))
    )
    (net (code "35") (name "unconnected-(U$1-MOBO_ON{slash}OFF-Pad19)") (class "Default")
      (node (ref "U$1") (pin "19") (pinfunction "MOBO_ON/OFF_19") (pintype "bidirectional"))
    )
    (net (code "36") (name "unconnected-(U$1-PWM_1-Pad20)") (class "Default")
      (node (ref "U$1") (pin "20") (pinfunction "PWM_1_20") (pintype "bidirectional"))
    )
    (net (code "37") (name "unconnected-(U$1-PWM_2-Pad21)") (class "Default")
      (node (ref "U$1") (pin "21") (pinfunction "PWM_2_21") (pintype "bidirectional"))
    )
    (net (code "38") (name "unconnected-(U$1-PWM_3-Pad22)") (class "Default")
      (node (ref "U$1") (pin "22") (pinfunction "PWM_3_22") (pintype "bidirectional"))
    )
    (net (code "39") (name "unconnected-(U$1-PWM_4-Pad23)") (class "Default")
      (node (ref "U$1") (pin "23") (pinfunction "PWM_4_23") (pintype "bidirectional"))
    )
    (net (code "40") (name "unconnected-(U$1-PWM_5-Pad24)") (class "Default")
      (node (ref "U$1") (pin "24") (pinfunction "PWM_5_24") (pintype "bidirectional"))
    )
    (net (code "41") (name "unconnected-(U$1-PWM_6-Pad25)") (class "Default")
      (node (ref "U$1") (pin "25") (pinfunction "PWM_6_25") (pintype "bidirectional"))
    )
    (net (code "42") (name "unconnected-(U$1-PWM_7-Pad26)") (class "Default")
      (node (ref "U$1") (pin "26") (pinfunction "PWM_7_26") (pintype "bidirectional"))
    )
    (net (code "43") (name "unconnected-(U$1-PWM_8-Pad27)") (class "Default")
      (node (ref "U$1") (pin "27") (pinfunction "PWM_8_27") (pintype "bidirectional"))
    )
    (net (code "44") (name "unconnected-(U$1-SPARE1-Pad7)") (class "Default")
      (node (ref "U$1") (pin "7") (pinfunction "SPARE1_7") (pintype "bidirectional"))
    )
    (net (code "45") (name "unconnected-(U$1-SPARE2-Pad28)") (class "Default")
      (node (ref "U$1") (pin "28") (pinfunction "SPARE2_28") (pintype "bidirectional"))
    )
    (net (code "46") (name "unconnected-(U$1-SPARE3-Pad33)") (class "Default")
      (node (ref "U$1") (pin "33") (pinfunction "SPARE3_33") (pintype "bidirectional"))
    )
    (net (code "47") (name "unconnected-(U$1-SPARE4-Pad34)") (class "Default")
      (node (ref "U$1") (pin "34") (pinfunction "SPARE4_34") (pintype "bidirectional"))
    )
    (net (code "48") (name "unconnected-(U$1-SPARE5-Pad35)") (class "Default")
      (node (ref "U$1") (pin "35") (pinfunction "SPARE5_35") (pintype "bidirectional"))
    )
    (net (code "49") (name "unconnected-(U$1-SPARE6-Pad36)") (class "Default")
      (node (ref "U$1") (pin "36") (pinfunction "SPARE6_36") (pintype "bidirectional"))
    )
    (net (code "50") (name "unconnected-(U$1-SPARE7-Pad43)") (class "Default")
      (node (ref "U$1") (pin "43") (pinfunction "SPARE7_43") (pintype "bidirectional"))
    )
    (net (code "51") (name "unconnected-(U$1-SPARE8-Pad50)") (class "Default")
      (node (ref "U$1") (pin "50") (pinfunction "SPARE8_50") (pintype "bidirectional"))
    )
    (net (code "52") (name "unconnected-(U$1-SWITCH_1-Pad38)") (class "Default")
      (node (ref "U$1") (pin "38") (pinfunction "SWITCH_1_38") (pintype "output"))
    )
    (net (code "53") (name "unconnected-(U$1-SWITCH_2-Pad39)") (class "Default")
      (node (ref "U$1") (pin "39") (pinfunction "SWITCH_2_39") (pintype "output"))
    )
    (net (code "54") (name "unconnected-(U$1-SWITCH_3-Pad40)") (class "Default")
      (node (ref "U$1") (pin "40") (pinfunction "SWITCH_3_40") (pintype "output"))
    )
    (net (code "55") (name "unconnected-(U$1-SWITCH_4-Pad41)") (class "Default")
      (node (ref "U$1") (pin "41") (pinfunction "SWITCH_4_41") (pintype "output"))
    )
    (net (code "56") (name "unconnected-(U$1-SWITCH_5-Pad42)") (class "Default")
      (node (ref "U$1") (pin "42") (pinfunction "SWITCH_5_42") (pintype "output"))
    )
    (net (code "57") (name "unconnected-(U$2-OFF-Pad3)") (class "Default")
      (node (ref "U$2") (pin "3") (pinfunction "OFF_3") (pintype "bidirectional"))
    )
    (net (code "58") (name "unconnected-(U$3-OFF-Pad3)") (class "Default")
      (node (ref "U$3") (pin "3") (pinfunction "OFF_3") (pintype "bidirectional"))
    )
    (net (code "59") (name "unconnected-(U$12-PadIN5)") (class "Default")
      (node (ref "U$12") (pin "IN5") (pinfunction "IN5_IN5") (pintype "bidirectional"))
    )
    (net (code "60") (name "unconnected-(U$12-PadIN6)") (class "Default")
      (node (ref "U$12") (pin "IN6") (pinfunction "IN6_IN6") (pintype "bidirectional"))
    )
    (net (code "61") (name "unconnected-(U$12-PadIN7)") (class "Default")
      (node (ref "U$12") (pin "IN7") (pinfunction "IN7_IN7") (pintype "bidirectional"))
    )
    (net (code "62") (name "unconnected-(U$12-PadINT)") (class "Default")
      (node (ref "U$12") (pin "INT") (pinfunction "INT_INT") (pintype "bidirectional"))
    )
  )
)
